# LDO.net
KiCad netlist of a schematic drawn in Altium Designer
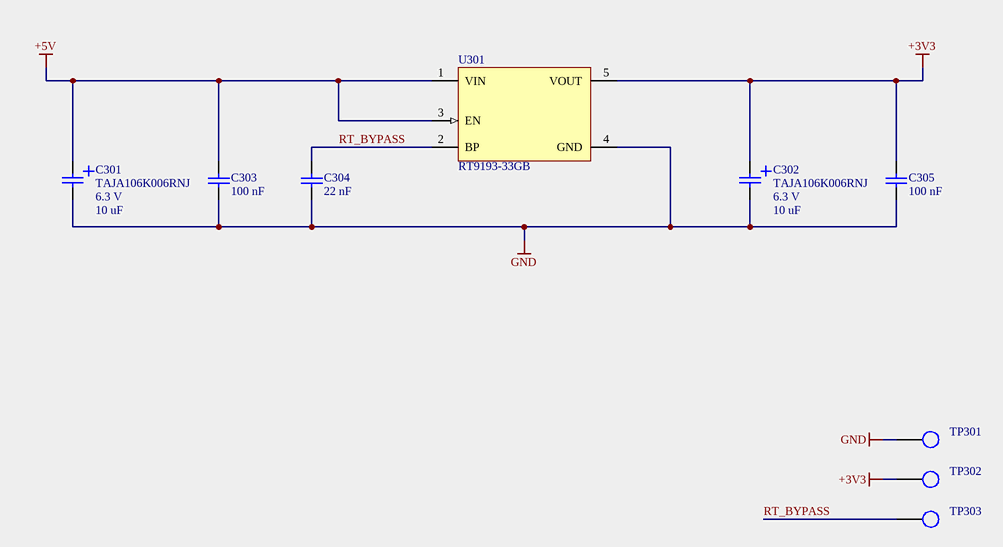
[diagram p0: LDO.SchDoc]

(export (version "E")
  (design (tool "Eeschema 10.0.6"))
  (components
    (comp (ref "C301")
      (value "CAP-10U-6V3_A")
      (footprint "CAPMP-A-1206-3216X18")
      (description "10uF ±10% 6.3V -55℃ ~ +125℃ Tantalum Capacitors")
      (fields
        (field (name "PARTNUMBER") "TAJA106K006RNJ")
        (field (name "VOLTAGE RATING") "6.3 V")
        (field (name "CAPACITANCE") "10 uF")
      )
      (libsource (lib "Конденсаторы танталовые") (part "CAP-10U-6V3_A"))
    )
    (comp (ref "C302")
      (value "CAP-10U-6V3_A")
      (footprint "CAPMP-A-1206-3216X18")
      (description "10uF ±10% 6.3V -55℃ ~ +125℃ Tantalum Capacitors")
      (fields
        (field (name "PARTNUMBER") "TAJA106K006RNJ")
        (field (name "VOLTAGE RATING") "6.3 V")
        (field (name "CAPACITANCE") "10 uF")
      )
      (libsource (lib "Конденсаторы танталовые") (part "CAP-10U-6V3_A"))
    )
    (comp (ref "C303")
      (value "CAP-100N")
      (footprint "CAPC0603")
      (description "Chip Capacitor, 100 nF, +/- 5%")
      (fields (field (name "TOLERANCE") "5 %") (field (name "CAPACITANCE") "100 nF"))
      (libsource (lib "Конденсаторы керамические SMD") (part "CAP-100N"))
    )
    (comp (ref "C304")
      (value "CAP-22N")
      (footprint "CAPC0603")
      (description "Chip Capacitor, 22 nF, +/- 5%")
      (fields (field (name "TOLERANCE") "5 %") (field (name "CAPACITANCE") "22 nF"))
      (libsource (lib "Конденсаторы керамические SMD") (part "CAP-22N"))
    )
    (comp (ref "C305")
      (value "CAP-100N")
      (footprint "CAPC0603")
      (description "Chip Capacitor, 100 nF, +/- 5%")
      (fields (field (name "TOLERANCE") "5 %") (field (name "CAPACITANCE") "100 nF"))
      (libsource (lib "Конденсаторы керамические SMD") (part "CAP-100N"))
    )
    (comp (ref "TP301") (value "~") (footprint "TP_C-0.5mm") (libsource (lib "Разъемы") (part "TestPad")))
    (comp (ref "TP302") (value "~") (footprint "TP_C-0.5mm") (libsource (lib "Разъемы") (part "TestPad")))
    (comp (ref "TP303") (value "~") (footprint "TP_C-0.5mm") (libsource (lib "Разъемы") (part "TestPad")))
    (comp (ref "U301")
      (value "RT9193-33GB")
      (footprint "SOT-23-5-RICHTEK")
      (description "Fixed 5.5V 3.3V 220mV @ 300mA SOT-23-5 Dropout Regulators(LDO)")
      (fields (field (name "PARTNUMBER") "RT9193-33GB"))
      (libsource (lib "Регуляотры напряжения") (part "RT9193-33GB"))
    )
  )
  (nets
    (net (code "1") (name "+3V3") (class "Default")
      (node (ref "C302") (pin "1") (pinfunction "1_1") (pintype "passive"))
      (node (ref "C305") (pin "2") (pinfunction "2_2") (pintype "passive"))
      (node (ref "TP302") (pin "1") (pintype "passive"))
      (node (ref "U301") (pin "5") (pinfunction "VOUT_5") (pintype "power_in"))
    )
    (net (code "2") (name "+5V") (class "Default")
      (node (ref "C301") (pin "1") (pinfunction "1_1") (pintype "passive"))
      (node (ref "C303") (pin "2") (pinfunction "2_2") (pintype "passive"))
      (node (ref "U301") (pin "1") (pinfunction "VIN_1") (pintype "power_in"))
      (node (ref "U301") (pin "3") (pinfunction "EN_3") (pintype "input"))
    )
    (net (code "3") (name "/RT_BYPASS") (class "Default")
      (node (ref "C304") (pin "2") (pinfunction "2_2") (pintype "passive"))
      (node (ref "TP303") (pin "1") (pintype "passive"))
      (node (ref "U301") (pin "2") (pinfunction "BP_2") (pintype "passive"))
    )
    (net (code "4") (name "GND") (class "Default")
      (node (ref "C301") (pin "2") (pinfunction "2_2") (pintype "passive"))
      (node (ref "C302") (pin "2") (pinfunction "2_2") (pintype "passive"))
      (node (ref "C303") (pin "1") (pinfunction "1_1") (pintype "passive"))
      (node (ref "C304") (pin "1") (pinfunction "1_1") (pintype "passive"))
      (node (ref "C305") (pin "1") (pinfunction "1_1") (pintype "passive"))
      (node (ref "TP301") (pin "1") (pintype "passive"))
      (node (ref "U301") (pin "4") (pinfunction "GND_4") (pintype "power_in"))
    )
  )
)
